# Scheme.net
KiCad netlist of a schematic drawn in Altium Designer
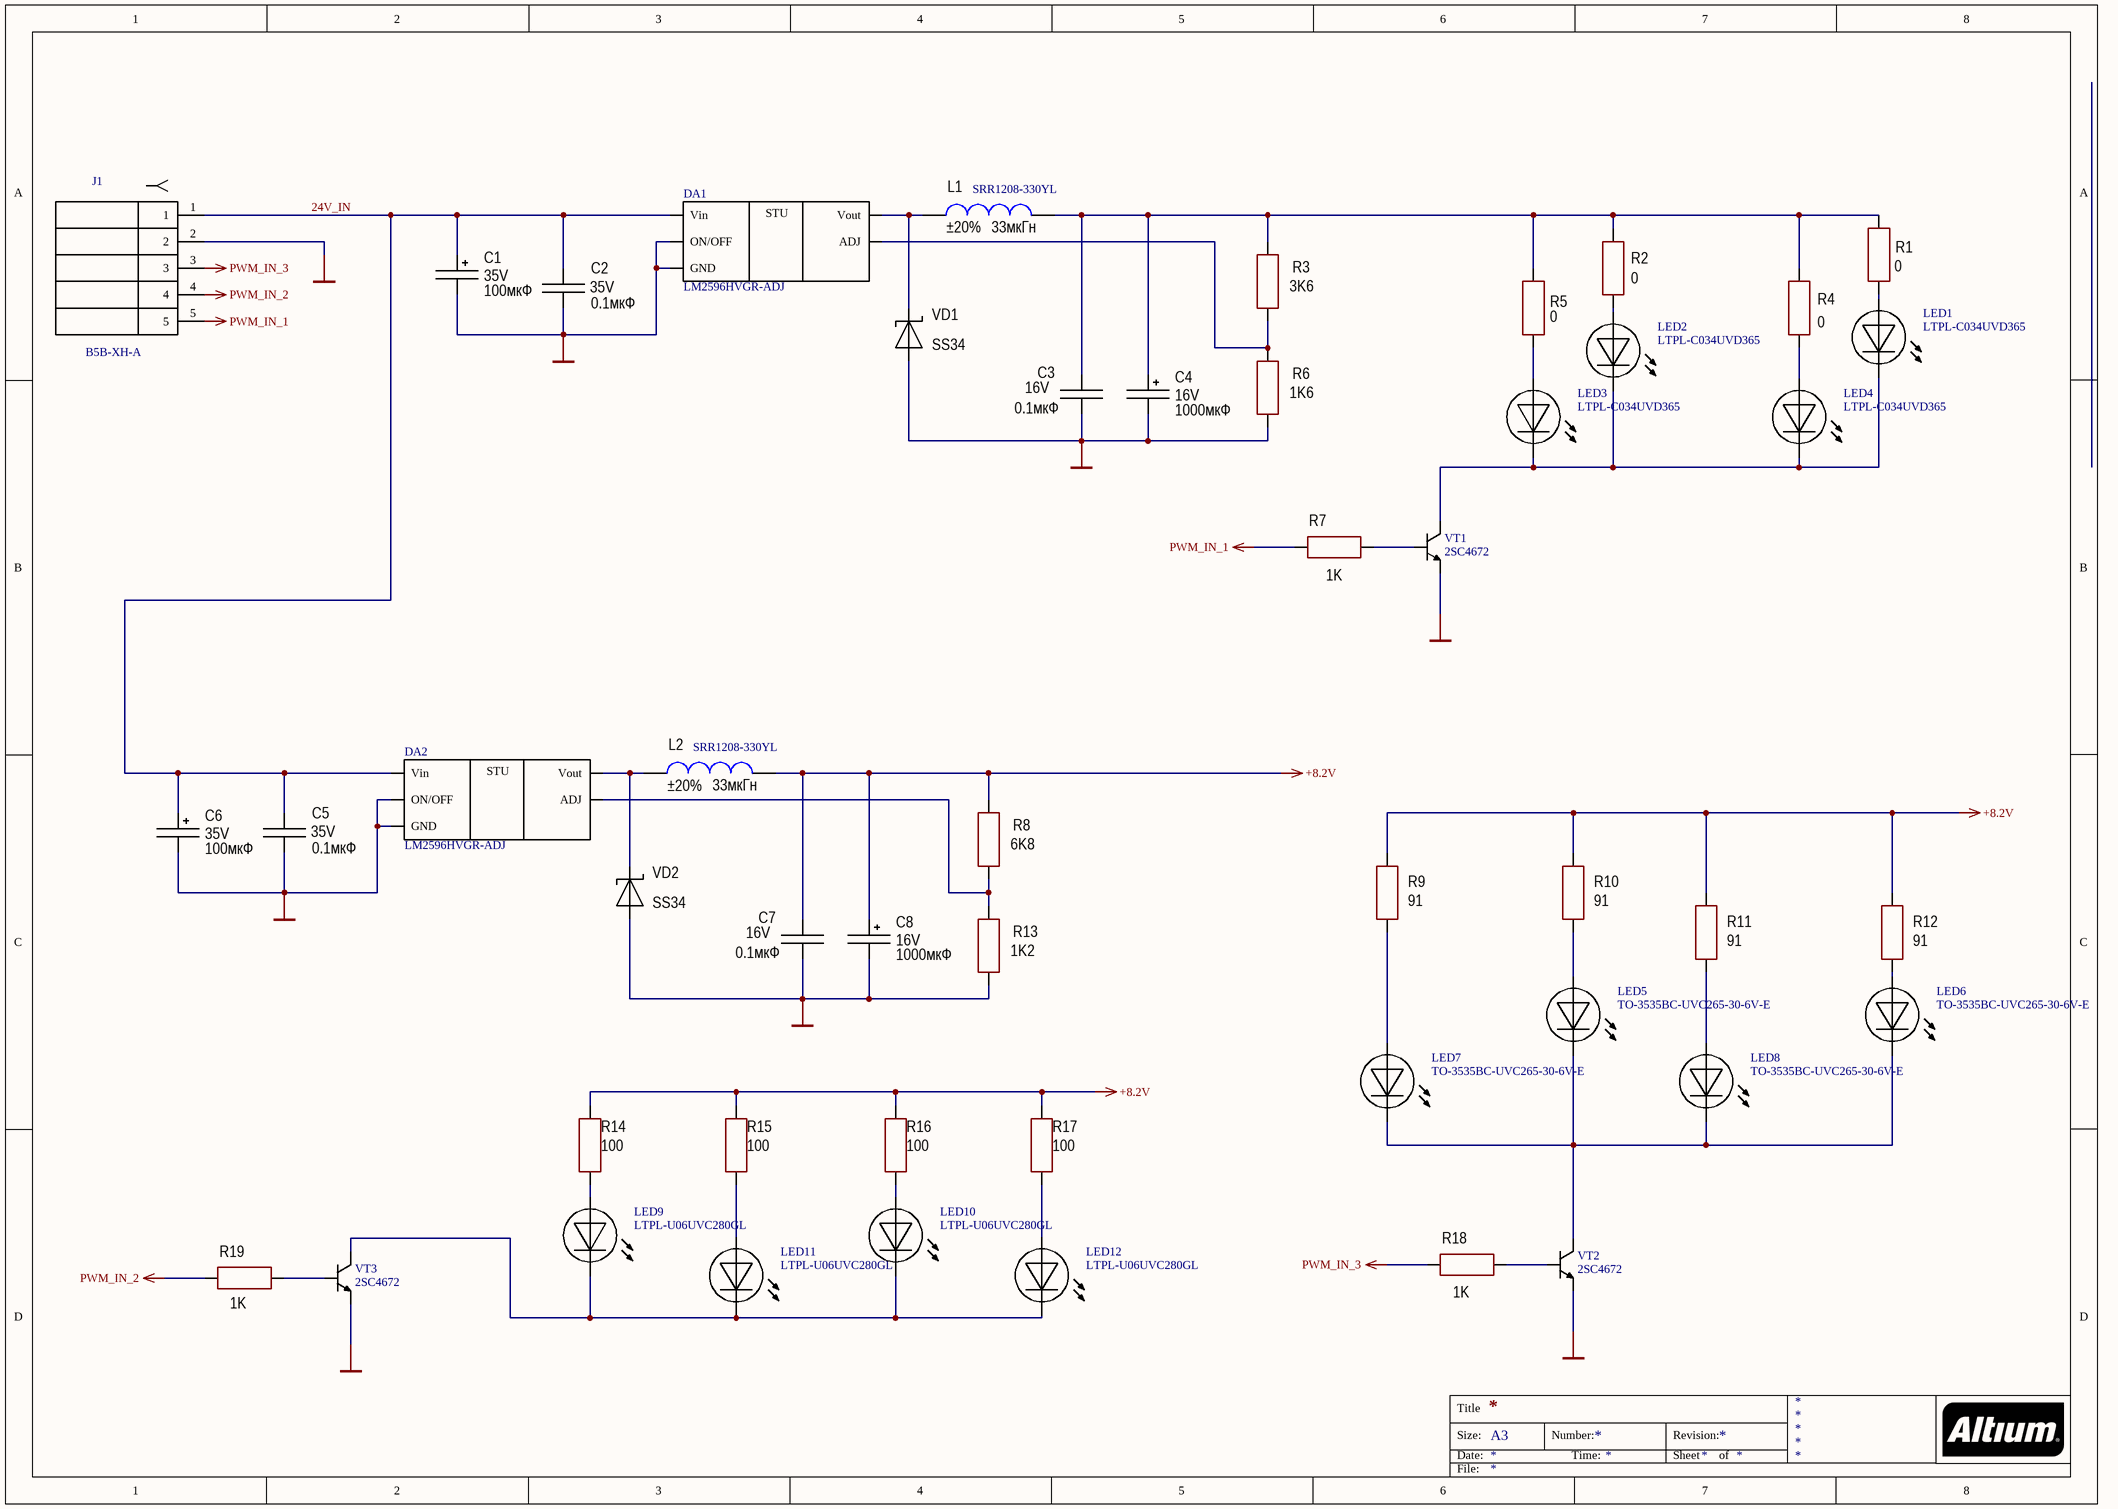
[diagram p0: Scheme.SchDoc]

(export (version "E")
  (design (tool "Eeschema 10.0.6"))
  (components
    (comp (ref "C1")
      (value "100мкФ")
      (footprint "CAP: D8C3.5H12")
      (fields
        (field (name "MANUFACTURER") "Wurth")
        (field (name "PARTNUMBER") "860080475013")
        (field (name "VALUEMANUFACTURERPARTNUMBER") "Aluminium capacitor, 100мкФ, 35V, ±20%, 54mOhm, 14x10x5 mm, -55...+105°C")
        (field (name "VOLTAGE") "35V")
      )
      (libsource (lib "Electromechanics") (part "Aluminium"))
    )
    (comp (ref "C2")
      (value "0.1мкФ")
      (footprint "CAP: 0805")
      (fields
        (field (name "MANUFACTURER") "Yageo")
        (field (name "PARTNUMBER") "CC0805KRX7R7BB104")
        (field (name "VALUEMANUFACTURERPARTNUMBER") "Ceramic capacitor, 0.1мкФ, X7R, ±10%, 35V, 0805, -55...+125°C")
        (field (name "VOLTAGE") "35V")
      )
      (libsource (lib "Capacitor") (part "Ceramic_0805"))
    )
    (comp (ref "C3")
      (value "0.1мкФ")
      (footprint "CAP: 0805")
      (fields
        (field (name "MANUFACTURER") "Yageo")
        (field (name "PARTNUMBER") "CC0805KRX7R7BB104")
        (field (name "VALUEMANUFACTURERPARTNUMBER") "Ceramic capacitor, 0.1мкФ, X7R, ±10%, 16V, 0805, -55...+125°C")
        (field (name "VOLTAGE") "16V")
      )
      (libsource (lib "Capacitor") (part "Ceramic_0805"))
    )
    (comp (ref "C4")
      (value "1000мкФ")
      (footprint "CAP: D8C3.5H12")
      (fields
        (field (name "MANUFACTURER") "Wurth")
        (field (name "PARTNUMBER") "860080475013")
        (field (name "VALUEMANUFACTURERPARTNUMBER") "Aluminium capacitor, 1000мкФ, 16V, ±20%, 54mOhm, 14x10x5 mm, -55...+105°C")
        (field (name "VOLTAGE") "16V")
      )
      (libsource (lib "Capacitor") (part "Aluminium"))
    )
    (comp (ref "C5")
      (value "0.1мкФ")
      (footprint "CAP: 0805")
      (fields
        (field (name "MANUFACTURER") "Yageo")
        (field (name "PARTNUMBER") "CC0805KRX7R7BB104")
        (field (name "VALUEMANUFACTURERPARTNUMBER") "Ceramic capacitor, 0.1мкФ, X7R, ±10%, 35V, 0805, -55...+125°C")
        (field (name "VOLTAGE") "35V")
      )
      (libsource (lib "Capacitor") (part "Ceramic_0805"))
    )
    (comp (ref "C6")
      (value "100мкФ")
      (footprint "CAP: D8C3.5H12")
      (fields
        (field (name "MANUFACTURER") "Wurth")
        (field (name "PARTNUMBER") "860080475013")
        (field (name "VALUEMANUFACTURERPARTNUMBER") "Aluminium capacitor, 100мкФ, 35V, ±20%, 54mOhm, 14x10x5 mm, -55...+105°C")
        (field (name "VOLTAGE") "35V")
      )
      (libsource (lib "Electromechanics") (part "Aluminium"))
    )
    (comp (ref "C7")
      (value "0.1мкФ")
      (footprint "CAP: 0805")
      (fields
        (field (name "MANUFACTURER") "Yageo")
        (field (name "PARTNUMBER") "CC0805KRX7R7BB104")
        (field (name "VALUEMANUFACTURERPARTNUMBER") "Ceramic capacitor, 0.1мкФ, X7R, ±10%, 16V, 0805, -55...+125°C")
        (field (name "VOLTAGE") "16V")
      )
      (libsource (lib "Capacitor") (part "Ceramic_0805"))
    )
    (comp (ref "C8")
      (value "1000мкФ")
      (footprint "CAP: D8C3.5H12")
      (fields
        (field (name "MANUFACTURER") "Wurth")
        (field (name "PARTNUMBER") "860080475013")
        (field (name "VALUEMANUFACTURERPARTNUMBER") "Aluminium capacitor, 1000мкФ, 16V, ±20%, 54mOhm, 14x10x5 mm, -55...+105°C")
        (field (name "VOLTAGE") "16V")
      )
      (libsource (lib "Capacitor") (part "Aluminium"))
    )
    (comp (ref "DA1")
      (value "LM2596HVGR-ADJ")
      (footprint "to-263-5l")
      (description "Step-down DC-DC, 3A")
      (libsource (lib "Schlib") (part "LM2596HVGR-ADJ"))
    )
    (comp (ref "DA2")
      (value "LM2596HVGR-ADJ")
      (footprint "to-263-5l")
      (description "Step-down DC-DC, 3A")
      (libsource (lib "Schlib") (part "LM2596HVGR-ADJ"))
    )
    (comp (ref "J1")
      (value "B5B-XH-A")
      (footprint "B5B-XH-A")
      (description "Connector")
      (libsource (lib "Schlib") (part "CONNECTOR_5PIN"))
    )
    (comp (ref "L1")
      (value "33мкГн")
      (footprint "SRR1208-330YL")
      (description "https://www.chipdip.ru/product/srr1208-330yl")
      (fields
        (field (name "MANUFACTURER") "Murata Electronics")
        (field (name "PARTNUMBER") "LQM21FN100M70L")
        (field (name "TOLERANCE") "±20%")
      )
      (libsource (lib "Inductor") (part "Inductor_0805"))
    )
    (comp (ref "L2")
      (value "33мкГн")
      (footprint "SRR1208-330YL")
      (description "https://www.chipdip.ru/product/srr1208-330yl")
      (fields
        (field (name "MANUFACTURER") "Murata Electronics")
        (field (name "PARTNUMBER") "LQM21FN100M70L")
        (field (name "TOLERANCE") "±20%")
      )
      (libsource (lib "Inductor") (part "Inductor_0805"))
    )
    (comp (ref "LED1")
      (value "LTPL-C034UVD365")
      (footprint "LTPL-C034UVD365")
      (description "UF-LED, 350mA")
      (libsource (lib "Schlib") (part "LTPL-C034UVD365"))
    )
    (comp (ref "LED2")
      (value "LTPL-C034UVD365")
      (footprint "LTPL-C034UVD365")
      (description "UF-LED, 350mA")
      (libsource (lib "Schlib") (part "LTPL-C034UVD365"))
    )
    (comp (ref "LED3")
      (value "LTPL-C034UVD365")
      (footprint "LTPL-C034UVD365")
      (description "UF-LED, 350mA")
      (libsource (lib "Schlib") (part "LTPL-C034UVD365"))
    )
    (comp (ref "LED4")
      (value "LTPL-C034UVD365")
      (footprint "LTPL-C034UVD365")
      (description "UF-LED, 350mA")
      (libsource (lib "Schlib") (part "LTPL-C034UVD365"))
    )
    (comp (ref "LED5")
      (value "TO-3535BC-UVC265-30-6V-E")
      (footprint "TO-3535BC-UVC265-30-6V-E")
      (description "UV-LED, 30mA")
      (libsource (lib "Schlib") (part "TO-3535BC-UVC265-30-6V-E"))
    )
    (comp (ref "LED6")
      (value "TO-3535BC-UVC265-30-6V-E")
      (footprint "TO-3535BC-UVC265-30-6V-E")
      (description "UV-LED, 30mA")
      (libsource (lib "Schlib") (part "TO-3535BC-UVC265-30-6V-E"))
    )
    (comp (ref "LED7")
      (value "TO-3535BC-UVC265-30-6V-E")
      (footprint "TO-3535BC-UVC265-30-6V-E")
      (description "UV-LED, 30mA")
      (libsource (lib "Schlib") (part "TO-3535BC-UVC265-30-6V-E"))
    )
    (comp (ref "LED8")
      (value "TO-3535BC-UVC265-30-6V-E")
      (footprint "TO-3535BC-UVC265-30-6V-E")
      (description "UV-LED, 30mA")
      (libsource (lib "Schlib") (part "TO-3535BC-UVC265-30-6V-E"))
    )
    (comp (ref "LED9")
      (value "LTPL-U06UVC280GL")
      (footprint "LTPL-U06UVC280GL")
      (description "UF-LED, 20mA")
      (libsource (lib "Schlib") (part "LTPL-U06UVC280GL"))
    )
    (comp (ref "LED10")
      (value "LTPL-U06UVC280GL")
      (footprint "LTPL-U06UVC280GL")
      (description "UF-LED, 20mA")
      (libsource (lib "Schlib") (part "LTPL-U06UVC280GL"))
    )
    (comp (ref "LED11")
      (value "LTPL-U06UVC280GL")
      (footprint "LTPL-U06UVC280GL")
      (description "UF-LED, 20mA")
      (libsource (lib "Schlib") (part "LTPL-U06UVC280GL"))
    )
    (comp (ref "LED12")
      (value "LTPL-U06UVC280GL")
      (footprint "LTPL-U06UVC280GL")
      (description "UF-LED, 20mA")
      (libsource (lib "Schlib") (part "LTPL-U06UVC280GL"))
    )
    (comp (ref "R1")
      (value "0")
      (footprint "RES: 0805")
      (fields
        (field (name "MANUFACTURER") "Yageo")
        (field (name "PARTNUMBER") "RC0805JR-07100RL")
        (field (name "VALUEMANUFACTURERPARTNUMBER") "Resistor film, 0, ±5%, 0805, 0.125W, -55...+125°C")
      )
      (libsource (lib "Resistor") (part "Resistor_0805"))
    )
    (comp (ref "R2")
      (value "0")
      (footprint "RES: 0805")
      (fields
        (field (name "MANUFACTURER") "Yageo")
        (field (name "PARTNUMBER") "RC0805JR-07100RL")
        (field (name "VALUEMANUFACTURERPARTNUMBER") "Resistor film, 0, ±5%, 0805, 0.125W, -55...+125°C")
      )
      (libsource (lib "Resistor") (part "Resistor_0805"))
    )
    (comp (ref "R3")
      (value "3K6")
      (footprint "RES: 0805")
      (fields
        (field (name "MANUFACTURER") "Yageo")
        (field (name "PARTNUMBER") "RC0805JR-07100RL")
        (field (name "VALUEMANUFACTURERPARTNUMBER") "Resistor film, 3K6, ±5%, 0805, 0.125W, -55...+125°C")
      )
      (libsource (lib "Resistor") (part "Resistor_0805"))
    )
    (comp (ref "R4")
      (value "0")
      (footprint "RES: 0805")
      (fields
        (field (name "MANUFACTURER") "Yageo")
        (field (name "PARTNUMBER") "RC0805JR-07100RL")
        (field (name "VALUEMANUFACTURERPARTNUMBER") "Resistor film, 0, ±5%, 0805, 0.125W, -55...+125°C")
      )
      (libsource (lib "Resistor") (part "Resistor_0805"))
    )
    (comp (ref "R5")
      (value "0")
      (footprint "RES: 0805")
      (fields
        (field (name "MANUFACTURER") "Yageo")
        (field (name "PARTNUMBER") "RC0805JR-07100RL")
        (field (name "VALUEMANUFACTURERPARTNUMBER") "Resistor film, 0, ±5%, 0805, 0.125W, -55...+125°C")
      )
      (libsource (lib "Resistor") (part "Resistor_0805"))
    )
    (comp (ref "R6")
      (value "1K6")
      (footprint "RES: 0805")
      (fields
        (field (name "MANUFACTURER") "Yageo")
        (field (name "PARTNUMBER") "RC0805JR-07100RL")
        (field (name "VALUEMANUFACTURERPARTNUMBER") "Resistor film, 1K6, ±5%, 0805, 0.125W, -55...+125°C")
      )
      (libsource (lib "Resistor") (part "Resistor_0805"))
    )
    (comp (ref "R7")
      (value "1K")
      (footprint "RES: 0805")
      (fields
        (field (name "MANUFACTURER") "Yageo")
        (field (name "PARTNUMBER") "RC0805JR-07100RL")
        (field (name "VALUEMANUFACTURERPARTNUMBER") "Resistor film, 1K, ±5%, 0805, 0.125W, -55...+125°C")
      )
      (libsource (lib "") (part "Resistor_0805_1"))
    )
    (comp (ref "R8")
      (value "6K8")
      (footprint "RES: 0805")
      (fields
        (field (name "MANUFACTURER") "Yageo")
        (field (name "PARTNUMBER") "RC0805JR-07100RL")
        (field (name "VALUEMANUFACTURERPARTNUMBER") "Resistor film, 6K8, ±5%, 0805, 0.125W, -55...+125°C")
      )
      (libsource (lib "Resistor") (part "Resistor_0805"))
    )
    (comp (ref "R9")
      (value "91")
      (footprint "RES: 0805")
      (fields
        (field (name "MANUFACTURER") "Yageo")
        (field (name "PARTNUMBER") "RC0805JR-07100RL")
        (field (name "VALUEMANUFACTURERPARTNUMBER") "Resistor film, 91, ±5%, 0805, 0.125W, -55...+125°C")
      )
      (libsource (lib "Resistor") (part "Resistor_0805"))
    )
    (comp (ref "R10")
      (value "91")
      (footprint "RES: 0805")
      (fields
        (field (name "MANUFACTURER") "Yageo")
        (field (name "PARTNUMBER") "RC0805JR-07100RL")
        (field (name "VALUEMANUFACTURERPARTNUMBER") "Resistor film, 91, ±5%, 0805, 0.125W, -55...+125°C")
      )
      (libsource (lib "Resistor") (part "Resistor_0805"))
    )
    (comp (ref "R11")
      (value "91")
      (footprint "RES: 0805")
      (fields
        (field (name "MANUFACTURER") "Yageo")
        (field (name "PARTNUMBER") "RC0805JR-07100RL")
        (field (name "VALUEMANUFACTURERPARTNUMBER") "Resistor film, 91, ±5%, 0805, 0.125W, -55...+125°C")
      )
      (libsource (lib "Resistor") (part "Resistor_0805"))
    )
    (comp (ref "R12")
      (value "91")
      (footprint "RES: 0805")
      (fields
        (field (name "MANUFACTURER") "Yageo")
        (field (name "PARTNUMBER") "RC0805JR-07100RL")
        (field (name "VALUEMANUFACTURERPARTNUMBER") "Resistor film, 91, ±5%, 0805, 0.125W, -55...+125°C")
      )
      (libsource (lib "Resistor") (part "Resistor_0805"))
    )
    (comp (ref "R13")
      (value "1K2")
      (footprint "RES: 0805")
      (fields
        (field (name "MANUFACTURER") "Yageo")
        (field (name "PARTNUMBER") "RC0805JR-07100RL")
        (field (name "VALUEMANUFACTURERPARTNUMBER") "Resistor film, 1K2, ±5%, 0805, 0.125W, -55...+125°C")
      )
      (libsource (lib "Resistor") (part "Resistor_0805"))
    )
    (comp (ref "R14")
      (value "100")
      (footprint "RES: 0805")
      (fields
        (field (name "MANUFACTURER") "Yageo")
        (field (name "PARTNUMBER") "RC0805JR-07100RL")
        (field (name "VALUEMANUFACTURERPARTNUMBER") "Resistor film, 100, ±5%, 0805, 0.125W, -55...+125°C")
      )
      (libsource (lib "") (part "Resistor_0805_2"))
    )
    (comp (ref "R15")
      (value "100")
      (footprint "RES: 0805")
      (fields
        (field (name "MANUFACTURER") "Yageo")
        (field (name "PARTNUMBER") "RC0805JR-07100RL")
        (field (name "VALUEMANUFACTURERPARTNUMBER") "Resistor film, 100, ±5%, 0805, 0.125W, -55...+125°C")
      )
      (libsource (lib "") (part "Resistor_0805_2"))
    )
    (comp (ref "R16")
      (value "100")
      (footprint "RES: 0805")
      (fields
        (field (name "MANUFACTURER") "Yageo")
        (field (name "PARTNUMBER") "RC0805JR-07100RL")
        (field (name "VALUEMANUFACTURERPARTNUMBER") "Resistor film, 100, ±5%, 0805, 0.125W, -55...+125°C")
      )
      (libsource (lib "") (part "Resistor_0805_2"))
    )
    (comp (ref "R17")
      (value "100")
      (footprint "RES: 0805")
      (fields
        (field (name "MANUFACTURER") "Yageo")
        (field (name "PARTNUMBER") "RC0805JR-07100RL")
        (field (name "VALUEMANUFACTURERPARTNUMBER") "Resistor film, 100, ±5%, 0805, 0.125W, -55...+125°C")
      )
      (libsource (lib "") (part "Resistor_0805_2"))
    )
    (comp (ref "R18")
      (value "1K")
      (footprint "RES: 0805")
      (fields
        (field (name "MANUFACTURER") "Yageo")
        (field (name "PARTNUMBER") "RC0805JR-07100RL")
        (field (name "VALUEMANUFACTURERPARTNUMBER") "Resistor film, 1K, ±5%, 0805, 0.125W, -55...+125°C")
      )
      (libsource (lib "") (part "Resistor_0805_1"))
    )
    (comp (ref "R19")
      (value "1K")
      (footprint "RES: 0805")
      (fields
        (field (name "MANUFACTURER") "Yageo")
        (field (name "PARTNUMBER") "RC0805JR-07100RL")
        (field (name "VALUEMANUFACTURERPARTNUMBER") "Resistor film, 1K, ±5%, 0805, 0.125W, -55...+125°C")
      )
      (libsource (lib "") (part "Resistor_0805_1"))
    )
    (comp (ref "VD1")
      (value "~")
      (footprint "DIODE: SMC")
      (description "https://www.chipdip.ru/product/srr1208-330yl")
      (fields
        (field (name "MANUFACTURER") "Diodes Incorporated")
        (field (name "VALUEMANUFACTURERPARTNUMBER") "Schottky diode, 80V, 500mA, 1V, 15pF, SOD-123, -55...+150°C")
        (field (name "PARTNUMBER") "SS34")
      )
      (libsource (lib "Diode") (part "Schottky_single"))
    )
    (comp (ref "VD2")
      (value "~")
      (footprint "DIODE: SMC")
      (description "https://www.chipdip.ru/product/srr1208-330yl")
      (fields
        (field (name "MANUFACTURER") "Diodes Incorporated")
        (field (name "VALUEMANUFACTURERPARTNUMBER") "Schottky diode, 80V, 500mA, 1V, 15pF, SOD-123, -55...+150°C")
        (field (name "PARTNUMBER") "SS34")
      )
      (libsource (lib "Diode") (part "Schottky_single"))
    )
    (comp (ref "VT1") (value "2SC4672") (footprint "2SC4672") (libsource (lib "Schlib") (part "2SC4672")))
    (comp (ref "VT2") (value "2SC4672") (footprint "2SC4672") (libsource (lib "Schlib") (part "2SC4672")))
    (comp (ref "VT3") (value "2SC4672") (footprint "2SC4672") (libsource (lib "Schlib") (part "2SC4672")))
  )
  (nets
    (net (code "1") (name "+8.2V") (class "Default")
      (node (ref "C7") (pin "2") (pinfunction "2_2") (pintype "power_in"))
      (node (ref "C8") (pin "1") (pinfunction "1_1") (pintype "power_in"))
      (node (ref "L2") (pin "1") (pinfunction "1_1") (pintype "passive"))
      (node (ref "R10") (pin "2") (pinfunction "2_2") (pintype "passive"))
      (node (ref "R11") (pin "2") (pinfunction "2_2") (pintype "passive"))
      (node (ref "R12") (pin "2") (pinfunction "2_2") (pintype "passive"))
      (node (ref "R14") (pin "1") (pinfunction "1_1") (pintype "passive"))
      (node (ref "R15") (pin "1") (pinfunction "1_1") (pintype "passive"))
      (node (ref "R16") (pin "1") (pinfunction "1_1") (pintype "passive"))
      (node (ref "R17") (pin "1") (pinfunction "1_1") (pintype "passive"))
      (node (ref "R8") (pin "2") (pinfunction "2_2") (pintype "passive"))
      (node (ref "R9") (pin "2") (pinfunction "2_2") (pintype "passive"))
    )
    (net (code "2") (name "/24V_IN") (class "Default")
      (node (ref "C1") (pin "1") (pinfunction "1_1") (pintype "power_in"))
      (node (ref "C2") (pin "2") (pinfunction "2_2") (pintype "power_in"))
      (node (ref "C5") (pin "2") (pinfunction "2_2") (pintype "power_in"))
      (node (ref "C6") (pin "1") (pinfunction "1_1") (pintype "power_in"))
      (node (ref "DA1") (pin "1") (pinfunction "Vin_1") (pintype "passive"))
      (node (ref "DA2") (pin "1") (pinfunction "Vin_1") (pintype "passive"))
      (node (ref "J1") (pin "1") (pinfunction "1_1") (pintype "passive"))
    )
    (net (code "3") (name "GND") (class "Default")
      (node (ref "C1") (pin "2") (pinfunction "2_2") (pintype "power_in"))
      (node (ref "C2") (pin "1") (pinfunction "1_1") (pintype "power_in"))
      (node (ref "C3") (pin "1") (pinfunction "1_1") (pintype "power_in"))
      (node (ref "C4") (pin "2") (pinfunction "2_2") (pintype "power_in"))
      (node (ref "C5") (pin "1") (pinfunction "1_1") (pintype "power_in"))
      (node (ref "C6") (pin "2") (pinfunction "2_2") (pintype "power_in"))
      (node (ref "C7") (pin "1") (pinfunction "1_1") (pintype "power_in"))
      (node (ref "C8") (pin "2") (pinfunction "2_2") (pintype "power_in"))
      (node (ref "DA1") (pin "3") (pinfunction "GND_3") (pintype "passive"))
      (node (ref "DA1") (pin "5") (pinfunction "ON/OFF_5") (pintype "passive"))
      (node (ref "DA2") (pin "3") (pinfunction "GND_3") (pintype "passive"))
      (node (ref "DA2") (pin "5") (pinfunction "ON/OFF_5") (pintype "passive"))
      (node (ref "J1") (pin "2") (pinfunction "2_2") (pintype "passive"))
      (node (ref "R13") (pin "1") (pinfunction "1_1") (pintype "passive"))
      (node (ref "R6") (pin "1") (pinfunction "1_1") (pintype "passive"))
      (node (ref "VD1") (pin "1") (pinfunction "1_1") (pintype "passive"))
      (node (ref "VD2") (pin "1") (pinfunction "1_1") (pintype "passive"))
      (node (ref "VT1") (pin "1") (pinfunction "E_1") (pintype "passive"))
      (node (ref "VT2") (pin "1") (pinfunction "E_1") (pintype "passive"))
      (node (ref "VT3") (pin "1") (pinfunction "E_1") (pintype "passive"))
    )
    (net (code "4") (name "Net-(C3-Pad2)") (class "Default")
      (node (ref "C3") (pin "2") (pinfunction "2_2") (pintype "power_in"))
      (node (ref "C4") (pin "1") (pinfunction "1_1") (pintype "power_in"))
      (node (ref "L1") (pin "1") (pinfunction "1_1") (pintype "passive"))
      (node (ref "R1") (pin "2") (pinfunction "2_2") (pintype "passive"))
      (node (ref "R2") (pin "2") (pinfunction "2_2") (pintype "passive"))
      (node (ref "R3") (pin "2") (pinfunction "2_2") (pintype "passive"))
      (node (ref "R4") (pin "2") (pinfunction "2_2") (pintype "passive"))
      (node (ref "R5") (pin "2") (pinfunction "2_2") (pintype "passive"))
    )
    (net (code "5") (name "Net-(DA1-ADJ)") (class "Default")
      (node (ref "DA1") (pin "4") (pinfunction "ADJ_4") (pintype "passive"))
      (node (ref "R3") (pin "1") (pinfunction "1_1") (pintype "passive"))
      (node (ref "R6") (pin "2") (pinfunction "2_2") (pintype "passive"))
    )
    (net (code "6") (name "Net-(DA1-Vout)") (class "Default")
      (node (ref "DA1") (pin "2") (pinfunction "Vout_2") (pintype "passive"))
      (node (ref "L1") (pin "2") (pinfunction "2_2") (pintype "passive"))
      (node (ref "VD1") (pin "2") (pinfunction "2_2") (pintype "passive"))
    )
    (net (code "7") (name "Net-(DA2-ADJ)") (class "Default")
      (node (ref "DA2") (pin "4") (pinfunction "ADJ_4") (pintype "passive"))
      (node (ref "R13") (pin "2") (pinfunction "2_2") (pintype "passive"))
      (node (ref "R8") (pin "1") (pinfunction "1_1") (pintype "passive"))
    )
    (net (code "8") (name "Net-(DA2-Vout)") (class "Default")
      (node (ref "DA2") (pin "2") (pinfunction "Vout_2") (pintype "passive"))
      (node (ref "L2") (pin "2") (pinfunction "2_2") (pintype "passive"))
      (node (ref "VD2") (pin "2") (pinfunction "2_2") (pintype "passive"))
    )
    (net (code "9") (name "Net-(LED1-A)") (class "Default")
      (node (ref "LED1") (pin "1") (pinfunction "A_1") (pintype "passive"))
      (node (ref "R1") (pin "1") (pinfunction "1_1") (pintype "passive"))
    )
    (net (code "10") (name "Net-(LED1-K)") (class "Default")
      (node (ref "LED1") (pin "2") (pinfunction "K_2") (pintype "passive"))
      (node (ref "LED2") (pin "2") (pinfunction "K_2") (pintype "passive"))
      (node (ref "LED3") (pin "2") (pinfunction "K_2") (pintype "passive"))
      (node (ref "LED4") (pin "2") (pinfunction "K_2") (pintype "passive"))
      (node (ref "VT1") (pin "2") (pinfunction "C_2") (pintype "passive"))
    )
    (net (code "11") (name "Net-(LED2-A)") (class "Default")
      (node (ref "LED2") (pin "1") (pinfunction "A_1") (pintype "passive"))
      (node (ref "R2") (pin "1") (pinfunction "1_1") (pintype "passive"))
    )
    (net (code "12") (name "Net-(LED3-A)") (class "Default")
      (node (ref "LED3") (pin "1") (pinfunction "A_1") (pintype "passive"))
      (node (ref "R5") (pin "1") (pinfunction "1_1") (pintype "passive"))
    )
    (net (code "13") (name "Net-(LED4-A)") (class "Default")
      (node (ref "LED4") (pin "1") (pinfunction "A_1") (pintype "passive"))
      (node (ref "R4") (pin "1") (pinfunction "1_1") (pintype "passive"))
    )
    (net (code "14") (name "Net-(LED5-A)") (class "Default")
      (node (ref "LED5") (pin "3") (pinfunction "A_3") (pintype "passive"))
      (node (ref "R10") (pin "1") (pinfunction "1_1") (pintype "passive"))
    )
    (net (code "15") (name "Net-(LED5-K)") (class "Default")
      (node (ref "LED5") (pin "4") (pinfunction "K_4") (pintype "passive"))
      (node (ref "LED6") (pin "4") (pinfunction "K_4") (pintype "passive"))
      (node (ref "LED7") (pin "4") (pinfunction "K_4") (pintype "passive"))
      (node (ref "LED8") (pin "4") (pinfunction "K_4") (pintype "passive"))
      (node (ref "VT2") (pin "2") (pinfunction "C_2") (pintype "passive"))
    )
    (net (code "16") (name "Net-(LED6-A)") (class "Default")
      (node (ref "LED6") (pin "3") (pinfunction "A_3") (pintype "passive"))
      (node (ref "R12") (pin "1") (pinfunction "1_1") (pintype "passive"))
    )
    (net (code "17") (name "Net-(LED7-A)") (class "Default")
      (node (ref "LED7") (pin "3") (pinfunction "A_3") (pintype "passive"))
      (node (ref "R9") (pin "1") (pinfunction "1_1") (pintype "passive"))
    )
    (net (code "18") (name "Net-(LED8-A)") (class "Default")
      (node (ref "LED8") (pin "3") (pinfunction "A_3") (pintype "passive"))
      (node (ref "R11") (pin "1") (pinfunction "1_1") (pintype "passive"))
    )
    (net (code "19") (name "Net-(LED9-A)") (class "Default")
      (node (ref "LED9") (pin "1") (pinfunction "A_1") (pintype "passive"))
      (node (ref "R14") (pin "2") (pinfunction "2_2") (pintype "passive"))
    )
    (net (code "20") (name "Net-(LED10-A)") (class "Default")
      (node (ref "LED10") (pin "1") (pinfunction "A_1") (pintype "passive"))
      (node (ref "R16") (pin "2") (pinfunction "2_2") (pintype "passive"))
    )
    (net (code "21") (name "Net-(LED10-K)") (class "Default")
      (node (ref "LED10") (pin "2") (pinfunction "K_2") (pintype "passive"))
      (node (ref "LED11") (pin "2") (pinfunction "K_2") (pintype "passive"))
      (node (ref "LED12") (pin "2") (pinfunction "K_2") (pintype "passive"))
      (node (ref "LED9") (pin "2") (pinfunction "K_2") (pintype "passive"))
      (node (ref "VT3") (pin "2") (pinfunction "C_2") (pintype "passive"))
    )
    (net (code "22") (name "Net-(LED11-A)") (class "Default")
      (node (ref "LED11") (pin "1") (pinfunction "A_1") (pintype "passive"))
      (node (ref "R15") (pin "2") (pinfunction "2_2") (pintype "passive"))
    )
    (net (code "23") (name "Net-(LED12-A)") (class "Default")
      (node (ref "LED12") (pin "1") (pinfunction "A_1") (pintype "passive"))
      (node (ref "R17") (pin "2") (pinfunction "2_2") (pintype "passive"))
    )
    (net (code "24") (name "Net-(VT1-B)") (class "Default")
      (node (ref "R7") (pin "2") (pinfunction "2_2") (pintype "passive"))
      (node (ref "VT1") (pin "3") (pinfunction "B_3") (pintype "passive"))
    )
    (net (code "25") (name "Net-(VT2-B)") (class "Default")
      (node (ref "R18") (pin "2") (pinfunction "2_2") (pintype "passive"))
      (node (ref "VT2") (pin "3") (pinfunction "B_3") (pintype "passive"))
    )
    (net (code "26") (name "Net-(VT3-B)") (class "Default")
      (node (ref "R19") (pin "2") (pinfunction "2_2") (pintype "passive"))
      (node (ref "VT3") (pin "3") (pinfunction "B_3") (pintype "passive"))
    )
    (net (code "27") (name "PWM_IN_1") (class "Default")
      (node (ref "J1") (pin "5") (pinfunction "5_5") (pintype "passive"))
      (node (ref "R7") (pin "1") (pinfunction "1_1") (pintype "passive"))
    )
    (net (code "28") (name "PWM_IN_2") (class "Default")
      (node (ref "J1") (pin "4") (pinfunction "4_4") (pintype "passive"))
      (node (ref "R19") (pin "1") (pinfunction "1_1") (pintype "passive"))
    )
    (net (code "29") (name "PWM_IN_3") (class "Default")
      (node (ref "J1") (pin "3") (pinfunction "3_3") (pintype "passive"))
      (node (ref "R18") (pin "1") (pinfunction "1_1") (pintype "passive"))
    )
  )
)
